# led-board.net
KiCad netlist of a schematic drawn in EAGLE
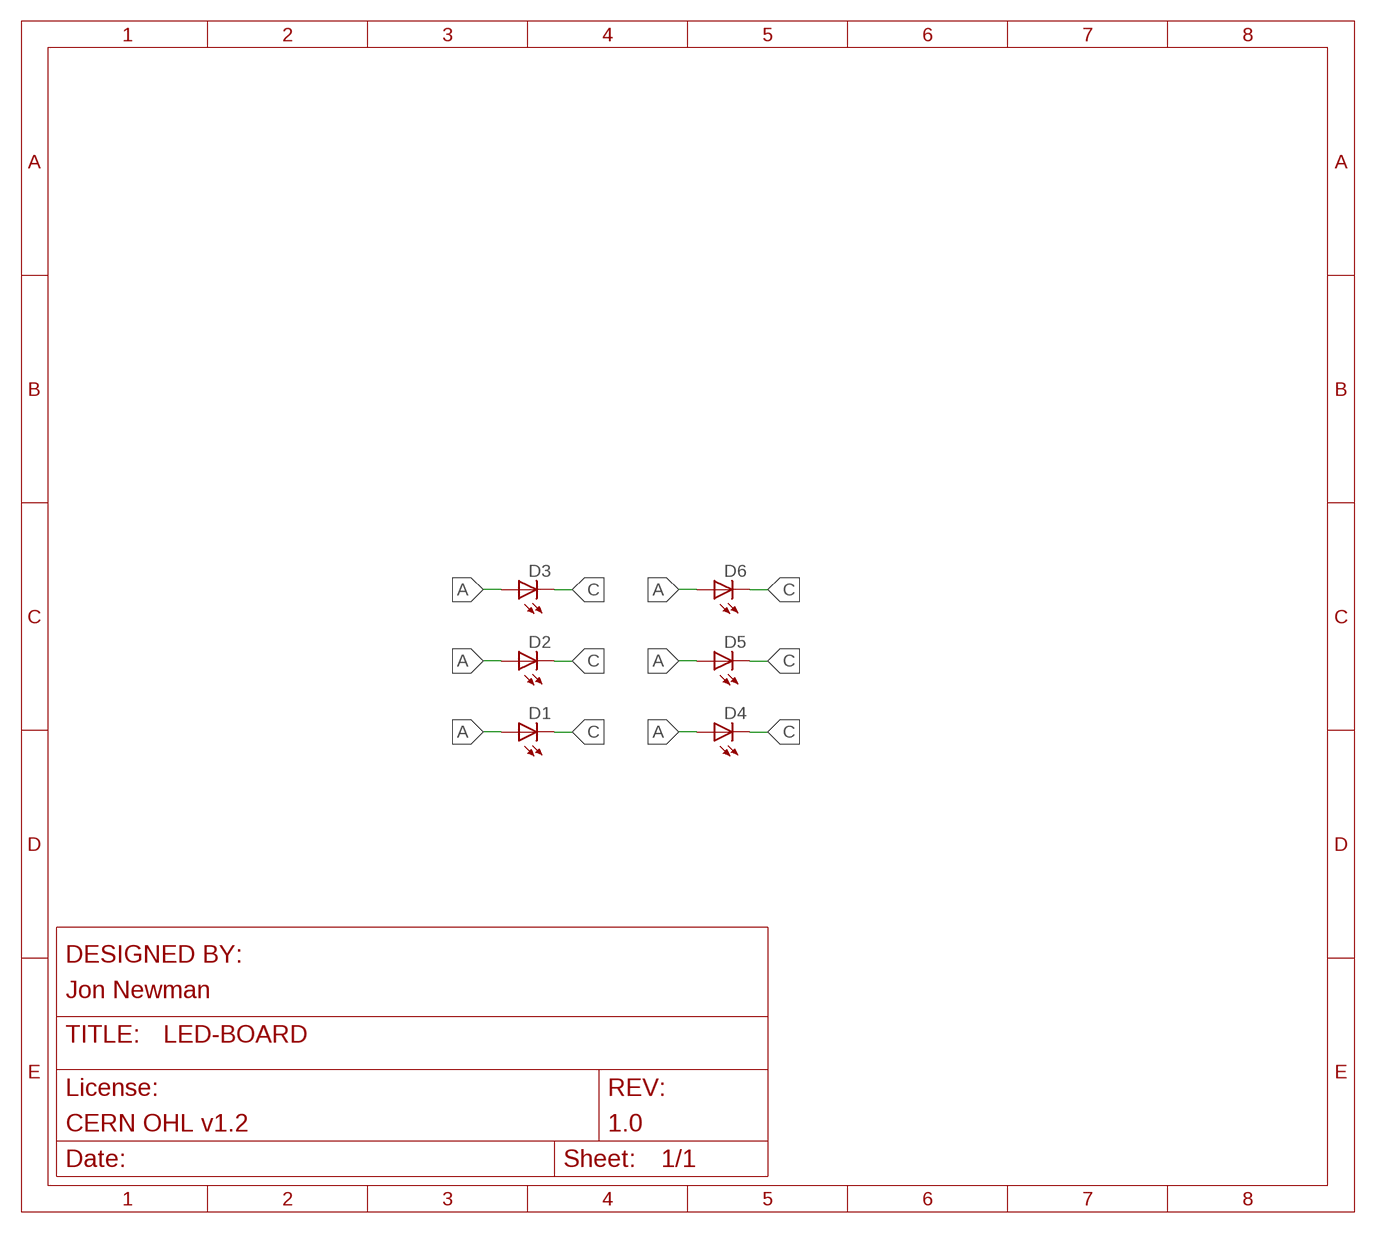
[diagram p0: schematic, sheet 1]

(export (version "E")
  (design (tool "Eeschema 10.0.6"))
  (components
    (comp (ref "D1")
      (value "LED_LXZ1")
      (footprint "eagle-import:LXZ1")
      (libsource (lib "eagle-import") (part "LED_LXZ1"))
    )
    (comp (ref "D2")
      (value "LED_LXZ1")
      (footprint "eagle-import:LXZ1")
      (libsource (lib "eagle-import") (part "LED_LXZ1"))
    )
    (comp (ref "D3")
      (value "LED_LXZ1")
      (footprint "eagle-import:LXZ1")
      (libsource (lib "eagle-import") (part "LED_LXZ1"))
    )
    (comp (ref "D4")
      (value "LED_LXZ1")
      (footprint "eagle-import:LXZ1")
      (libsource (lib "eagle-import") (part "LED_LXZ1"))
    )
    (comp (ref "D5")
      (value "LED_LXZ1")
      (footprint "eagle-import:LXZ1")
      (libsource (lib "eagle-import") (part "LED_LXZ1"))
    )
    (comp (ref "D6")
      (value "LED_LXZ1")
      (footprint "eagle-import:LXZ1")
      (libsource (lib "eagle-import") (part "LED_LXZ1"))
    )
  )
  (nets
    (net (code "1") (name "A") (class "Default")
      (node (ref "D1") (pin "A") (pinfunction "A_A") (pintype "passive"))
      (node (ref "D2") (pin "A") (pinfunction "A_A") (pintype "passive"))
      (node (ref "D3") (pin "A") (pinfunction "A_A") (pintype "passive"))
      (node (ref "D4") (pin "A") (pinfunction "A_A") (pintype "passive"))
      (node (ref "D5") (pin "A") (pinfunction "A_A") (pintype "passive"))
      (node (ref "D6") (pin "A") (pinfunction "A_A") (pintype "passive"))
    )
    (net (code "2") (name "C") (class "Default")
      (node (ref "D1") (pin "C") (pinfunction "C_C") (pintype "passive"))
      (node (ref "D2") (pin "C") (pinfunction "C_C") (pintype "passive"))
      (node (ref "D3") (pin "C") (pinfunction "C_C") (pintype "passive"))
      (node (ref "D4") (pin "C") (pinfunction "C_C") (pintype "passive"))
      (node (ref "D5") (pin "C") (pinfunction "C_C") (pintype "passive"))
      (node (ref "D6") (pin "C") (pinfunction "C_C") (pintype "passive"))
    )
  )
)
